# arduinoVisor3.net
KiCad netlist of a schematic drawn in EAGLE
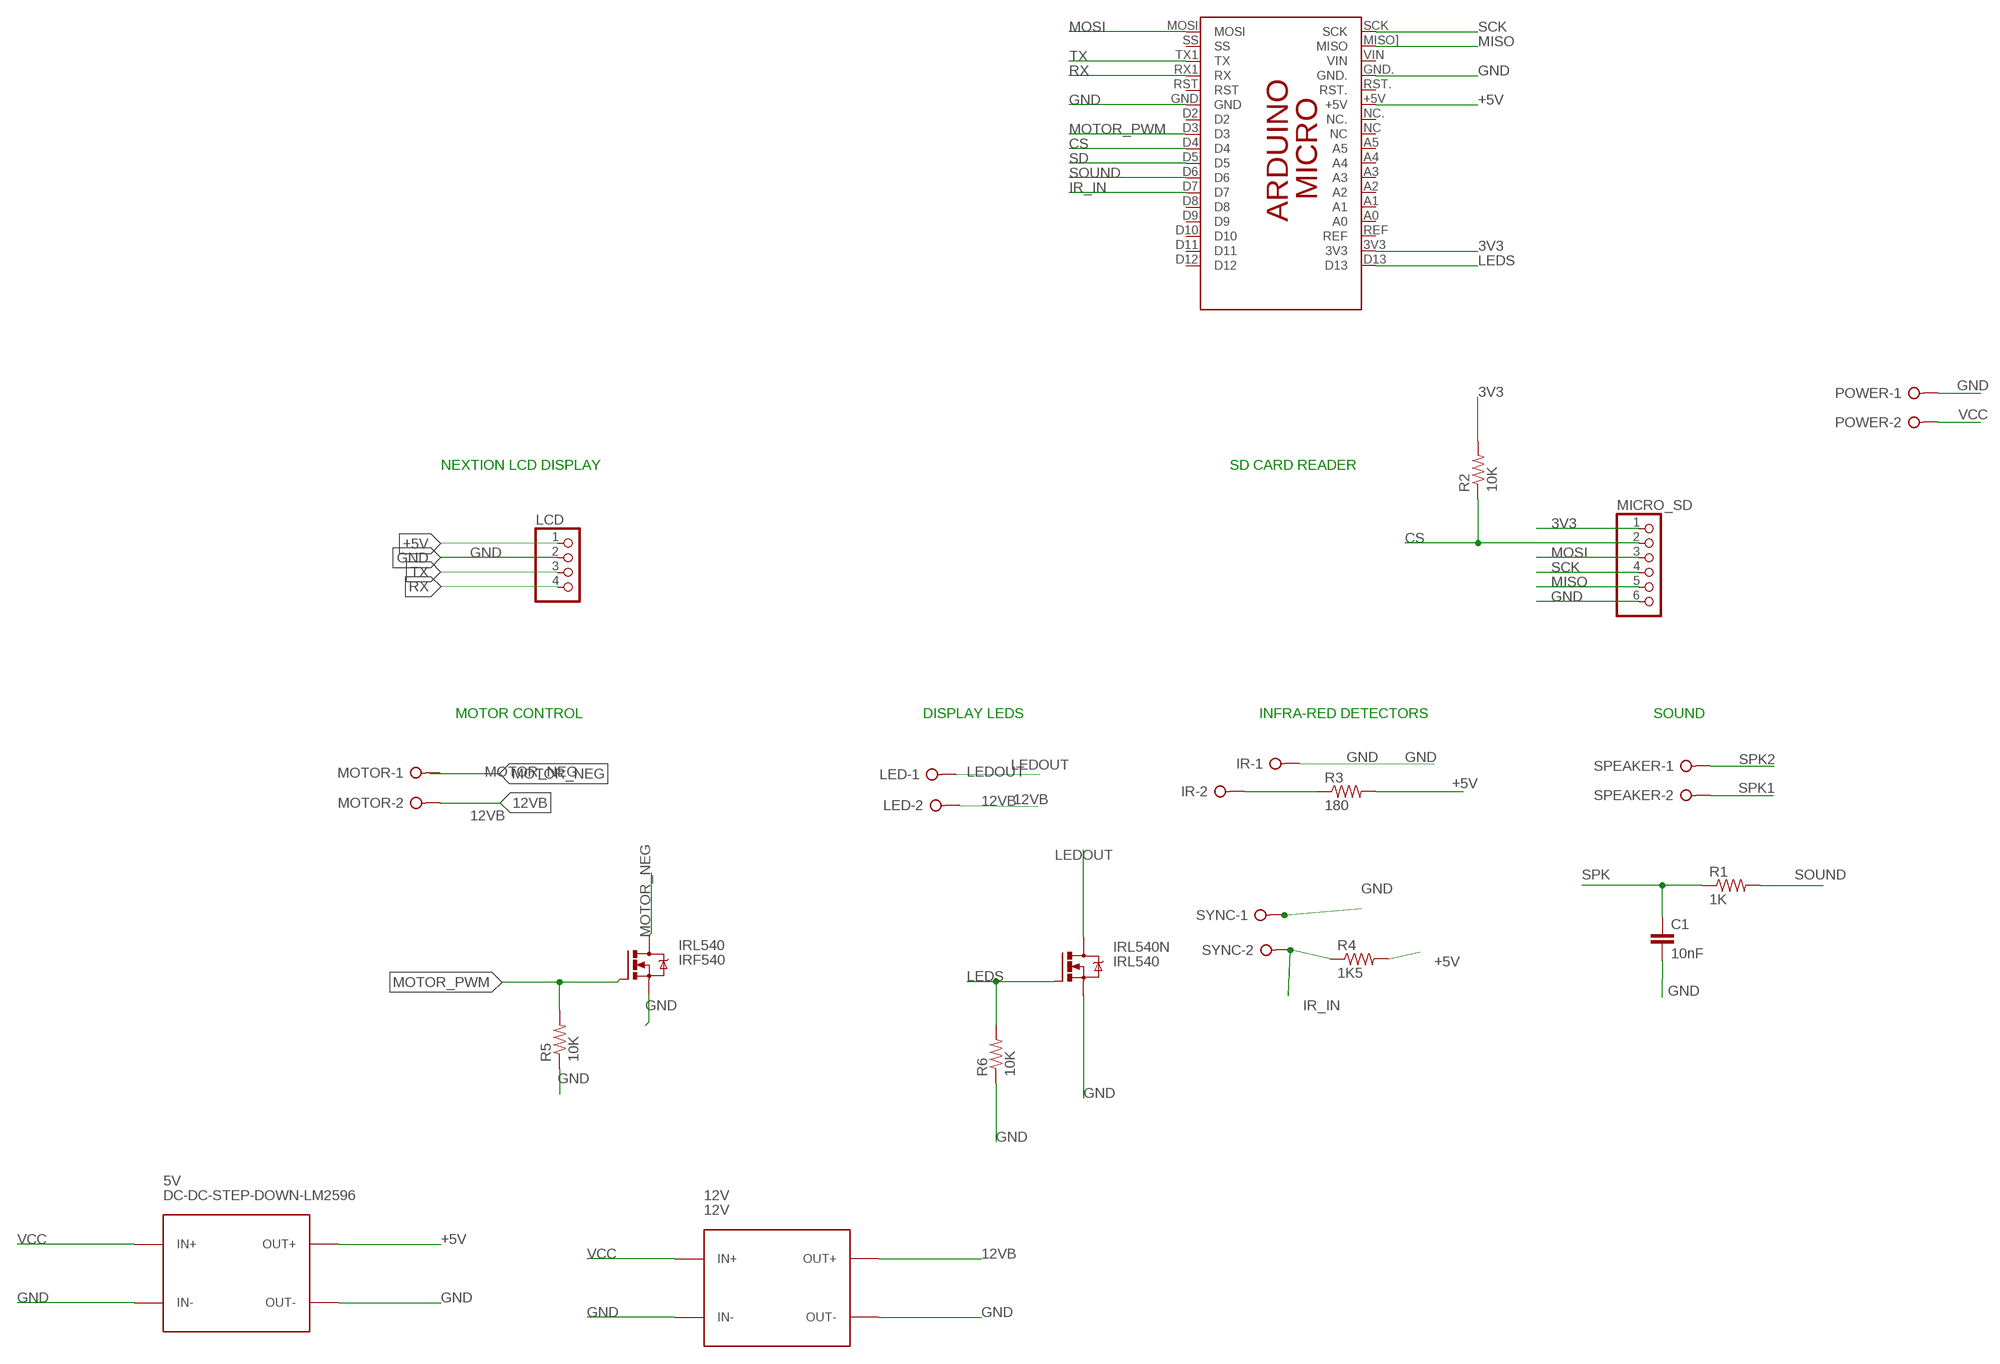
[diagram p0: schematic, sheet 1]
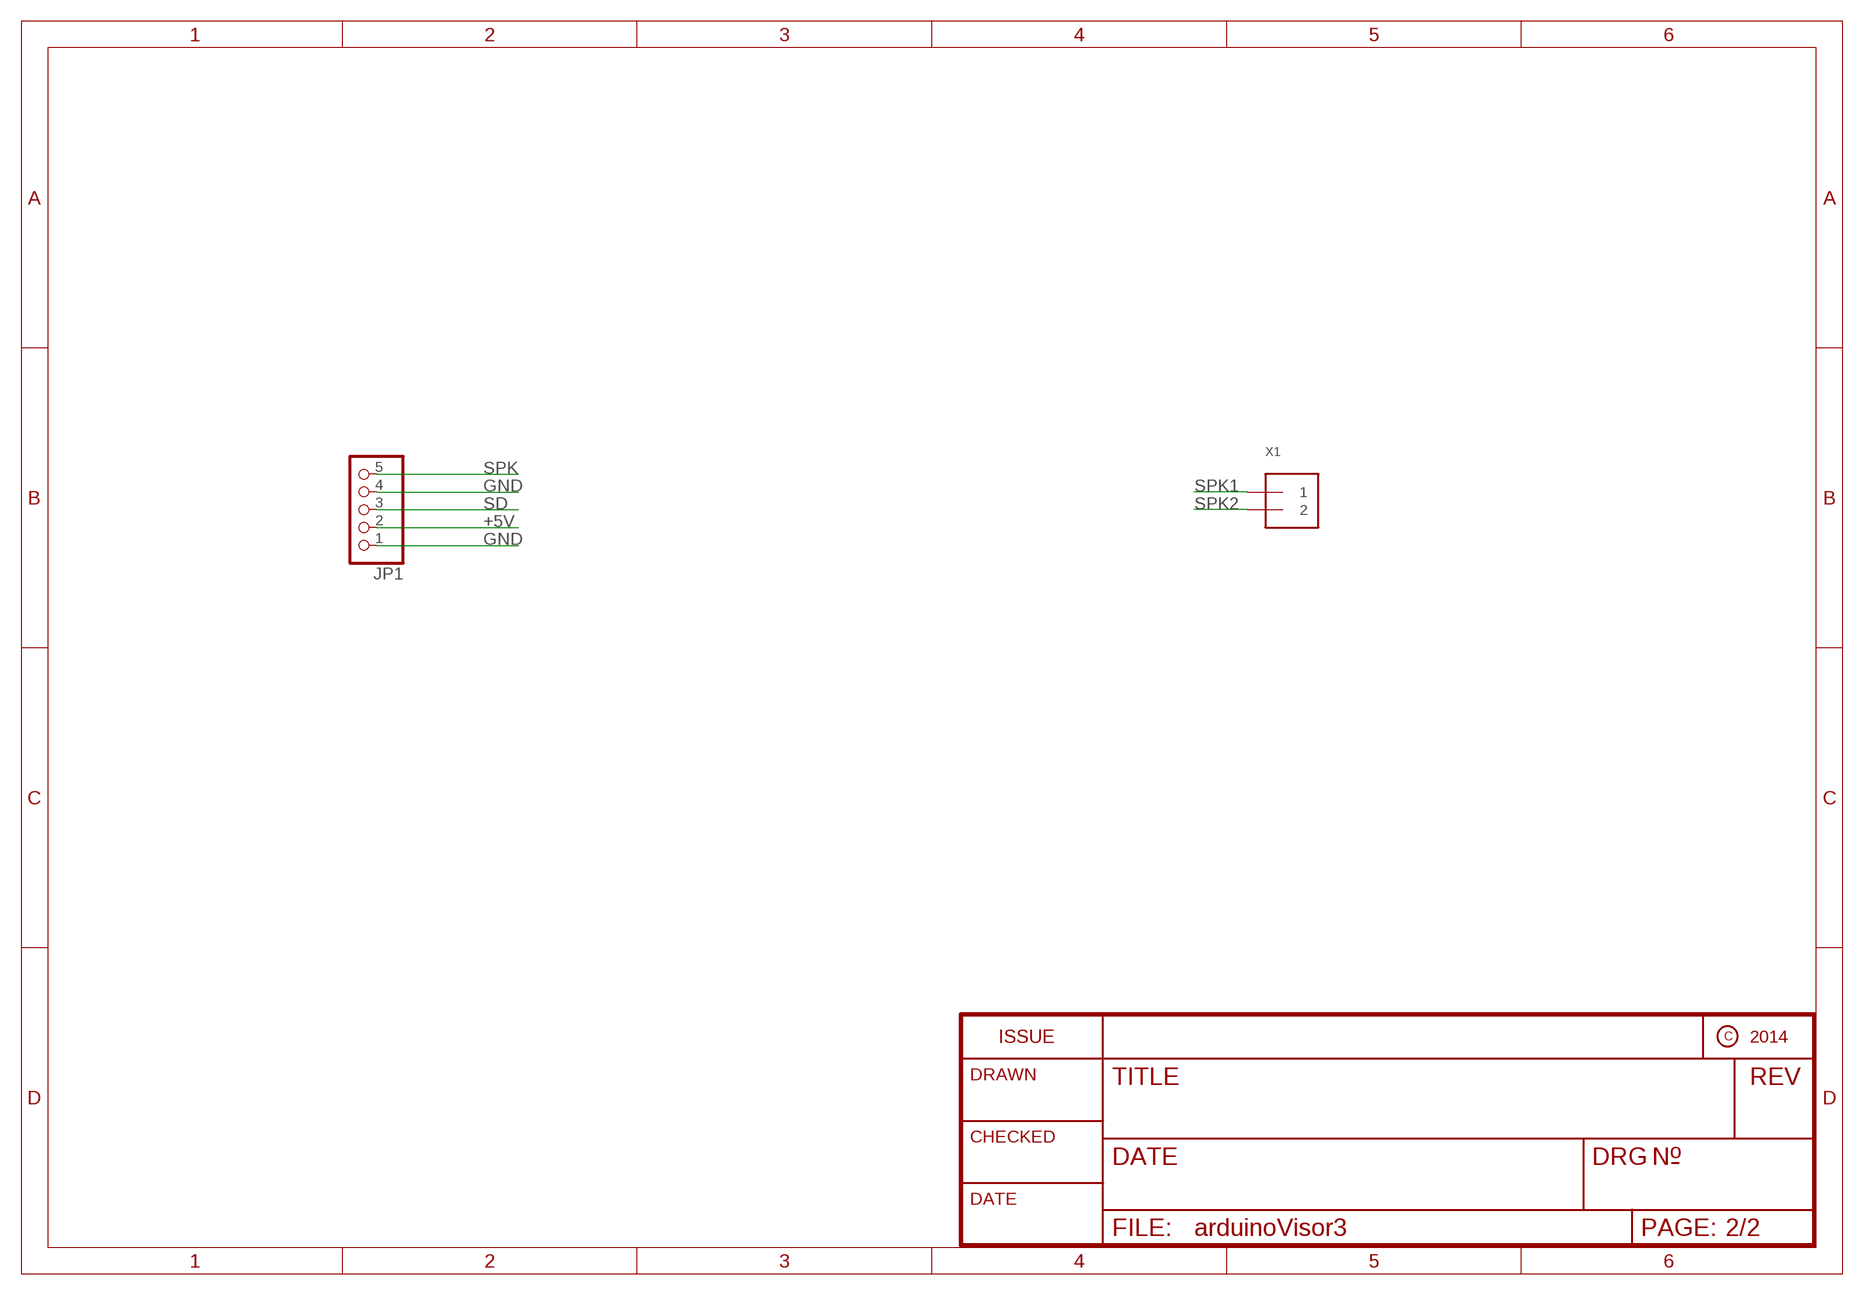
[diagram p1: schematic, sheet 2]

(export (version "E")
  (design (tool "Eeschema 10.0.6"))
  (components
    (comp (ref "5V")
      (value "DC-DC-STEP-DOWN-LM2596")
      (footprint "eagle-import:DC-DC-STEP-DOWN-LM2596")
      (libsource (lib "eagle-import") (part "DC-DC-STEP-DOWN-LM2596"))
    )
    (comp (ref "12V")
      (value "12V")
      (footprint "eagle-import:DC-DC-STEP-DOWN-LM2596")
      (libsource (lib "eagle-import") (part "DC-DC-STEP-DOWN-LM2596"))
    )
    (comp (ref "C1")
      (value "10nF")
      (footprint "eagle-import:C2.5-2")
      (libsource (lib "eagle-import") (part "C2.5/2"))
    )
    (comp (ref "IR")
      (value "W237-02P")
      (footprint "eagle-import:W237-132")
      (libsource (lib "eagle-import") (part "W237-02P"))
    )
    (comp (ref "IRL540")
      (value "IRF540")
      (footprint "eagle-import:TO220BV")
      (libsource (lib "eagle-import") (part "IRF540"))
    )
    (comp (ref "IRL540N")
      (value "IRL540")
      (footprint "eagle-import:TO220BV")
      (libsource (lib "eagle-import") (part "IRF540"))
    )
    (comp (ref "LCD")
      (value "PINHD-1X4")
      (footprint "eagle-import:1X04")
      (libsource (lib "eagle-import") (part "PINHD-1X4"))
    )
    (comp (ref "LED")
      (value "W237-02P")
      (footprint "eagle-import:W237-132")
      (libsource (lib "eagle-import") (part "W237-02P"))
    )
    (comp (ref "MICRO_SD")
      (value "PINHD-1X6")
      (footprint "eagle-import:1X06")
      (libsource (lib "eagle-import") (part "PINHD-1X6"))
    )
    (comp (ref "MOTOR")
      (value "W237-02P")
      (footprint "eagle-import:W237-132")
      (libsource (lib "eagle-import") (part "W237-02P"))
    )
    (comp (ref "PCB2")
      (value "ARDUINO_MICRO")
      (footprint "eagle-import:ARDUINO_MICRO")
      (libsource (lib "eagle-import") (part "ARDUINO_MICRO"))
    )
    (comp (ref "POWER")
      (value "W237-02P")
      (footprint "eagle-import:W237-132")
      (libsource (lib "eagle-import") (part "W237-02P"))
    )
    (comp (ref "R1")
      (value "1K")
      (footprint "eagle-import:0207_10")
      (libsource (lib "eagle-import") (part "R-US_0207/10"))
    )
    (comp (ref "R2")
      (value "10K")
      (footprint "eagle-import:0207_10")
      (libsource (lib "eagle-import") (part "R-US_0207/10"))
    )
    (comp (ref "R3")
      (value "180")
      (footprint "eagle-import:0207_10")
      (libsource (lib "eagle-import") (part "R-US_0207/10"))
    )
    (comp (ref "R4")
      (value "1K5")
      (footprint "eagle-import:0207_10")
      (libsource (lib "eagle-import") (part "R-US_0207/10"))
    )
    (comp (ref "R5")
      (value "10K")
      (footprint "eagle-import:0207_10")
      (libsource (lib "eagle-import") (part "R-US_0207/10"))
    )
    (comp (ref "R6")
      (value "10K")
      (footprint "eagle-import:0207_10")
      (libsource (lib "eagle-import") (part "R-US_0207/10"))
    )
    (comp (ref "SPEAKER")
      (value "W237-02P")
      (footprint "eagle-import:W237-132")
      (libsource (lib "eagle-import") (part "W237-02P"))
    )
    (comp (ref "SYNC")
      (value "W237-02P")
      (footprint "eagle-import:W237-132")
      (libsource (lib "eagle-import") (part "W237-02P"))
    )
    (comp (ref "JP1")
      (value "HEADER-1X570MIL")
      (footprint "eagle-import:1X05_ROUND_70")
      (libsource (lib "eagle-import") (part "HEADER-1X570MIL"))
    )
    (comp (ref "X1")
      (value "TERMBLOCK_1X2")
      (footprint "eagle-import:TERMBLOCK_1X2-3.5MM")
      (libsource (lib "eagle-import") (part "TERMBLOCK_1X2"))
    )
  )
  (nets
    (net (code "1") (name "+5V") (class "Default")
      (node (ref "5V") (pin "OUT+") (pinfunction "OUT+_OUT+") (pintype "bidirectional"))
      (node (ref "JP1") (pin "2") (pinfunction "2_2") (pintype "passive"))
      (node (ref "LCD") (pin "1") (pinfunction "1_1") (pintype "passive"))
      (node (ref "PCB2") (pin "+5V") (pinfunction "+5V_+5V") (pintype "bidirectional"))
      (node (ref "R3") (pin "2") (pinfunction "2_2") (pintype "passive"))
      (node (ref "R4") (pin "2") (pinfunction "2_2") (pintype "passive"))
    )
    (net (code "2") (name "3V3") (class "Default")
      (node (ref "MICRO_SD") (pin "1") (pinfunction "1_1") (pintype "passive"))
      (node (ref "PCB2") (pin "3V3") (pinfunction "3V3_3V3") (pintype "bidirectional"))
      (node (ref "R2") (pin "2") (pinfunction "2_2") (pintype "passive"))
    )
    (net (code "3") (name "12VB") (class "Default")
      (node (ref "12V") (pin "OUT+") (pinfunction "OUT+_OUT+") (pintype "bidirectional"))
      (node (ref "LED") (pin "2") (pinfunction "KL_2") (pintype "passive"))
      (node (ref "MOTOR") (pin "2") (pinfunction "KL_2") (pintype "passive"))
    )
    (net (code "4") (name "CS") (class "Default")
      (node (ref "MICRO_SD") (pin "2") (pinfunction "2_2") (pintype "passive"))
      (node (ref "PCB2") (pin "D4") (pinfunction "D4_D4") (pintype "bidirectional"))
      (node (ref "R2") (pin "1") (pinfunction "1_1") (pintype "passive"))
    )
    (net (code "5") (name "GND") (class "Default")
      (node (ref "12V") (pin "IN-") (pinfunction "IN-_IN-") (pintype "bidirectional"))
      (node (ref "12V") (pin "OUT-") (pinfunction "OUT-_OUT-") (pintype "bidirectional"))
      (node (ref "5V") (pin "IN-") (pinfunction "IN-_IN-") (pintype "bidirectional"))
      (node (ref "5V") (pin "OUT-") (pinfunction "OUT-_OUT-") (pintype "bidirectional"))
      (node (ref "C1") (pin "2") (pinfunction "2_2") (pintype "passive"))
      (node (ref "IR") (pin "1") (pinfunction "KL_1") (pintype "passive"))
      (node (ref "IRL540") (pin "S") (pinfunction "S_S") (pintype "passive"))
      (node (ref "IRL540N") (pin "S") (pinfunction "S_S") (pintype "passive"))
      (node (ref "JP1") (pin "1") (pinfunction "1_1") (pintype "passive"))
      (node (ref "JP1") (pin "4") (pinfunction "4_4") (pintype "passive"))
      (node (ref "LCD") (pin "2") (pinfunction "2_2") (pintype "passive"))
      (node (ref "MICRO_SD") (pin "6") (pinfunction "6_6") (pintype "passive"))
      (node (ref "PCB2") (pin "GND") (pinfunction "GND_GND") (pintype "bidirectional"))
      (node (ref "PCB2") (pin "GND.") (pinfunction "GND._GND.") (pintype "bidirectional"))
      (node (ref "POWER") (pin "1") (pinfunction "KL_1") (pintype "passive"))
      (node (ref "R5") (pin "1") (pinfunction "1_1") (pintype "passive"))
      (node (ref "R6") (pin "1") (pinfunction "1_1") (pintype "passive"))
      (node (ref "SYNC") (pin "1") (pinfunction "KL_1") (pintype "passive"))
    )
    (net (code "6") (name "IR_IN") (class "Default")
      (node (ref "PCB2") (pin "D7") (pinfunction "D7_D7") (pintype "bidirectional"))
      (node (ref "R4") (pin "1") (pinfunction "1_1") (pintype "passive"))
      (node (ref "SYNC") (pin "2") (pinfunction "KL_2") (pintype "passive"))
    )
    (net (code "7") (name "LEDOUT") (class "Default")
      (node (ref "IRL540N") (pin "D") (pinfunction "D_D") (pintype "passive"))
      (node (ref "LED") (pin "1") (pinfunction "KL_1") (pintype "passive"))
    )
    (net (code "8") (name "LEDS") (class "Default")
      (node (ref "IRL540N") (pin "G") (pinfunction "G_G") (pintype "passive"))
      (node (ref "PCB2") (pin "D13") (pinfunction "D13_D13") (pintype "bidirectional"))
      (node (ref "R6") (pin "2") (pinfunction "2_2") (pintype "passive"))
    )
    (net (code "9") (name "MISO") (class "Default")
      (node (ref "MICRO_SD") (pin "5") (pinfunction "5_5") (pintype "passive"))
      (node (ref "PCB2") (pin "MISO]") (pinfunction "MISO_MISO]") (pintype "bidirectional"))
    )
    (net (code "10") (name "MOSI") (class "Default")
      (node (ref "MICRO_SD") (pin "3") (pinfunction "3_3") (pintype "passive"))
      (node (ref "PCB2") (pin "MOSI") (pinfunction "MOSI_MOSI") (pintype "bidirectional"))
    )
    (net (code "11") (name "MOTOR_NEG") (class "Default")
      (node (ref "IRL540") (pin "D") (pinfunction "D_D") (pintype "passive"))
      (node (ref "MOTOR") (pin "1") (pinfunction "KL_1") (pintype "passive"))
    )
    (net (code "12") (name "MOTOR_PWM") (class "Default")
      (node (ref "IRL540") (pin "G") (pinfunction "G_G") (pintype "passive"))
      (node (ref "PCB2") (pin "D3") (pinfunction "D3_D3") (pintype "bidirectional"))
      (node (ref "R5") (pin "2") (pinfunction "2_2") (pintype "passive"))
    )
    (net (code "13") (name "Net-(IRB-KL)") (class "Default")
      (node (ref "IR") (pin "2") (pinfunction "KL_2") (pintype "passive"))
      (node (ref "R3") (pin "1") (pinfunction "1_1") (pintype "passive"))
    )
    (net (code "14") (name "RX") (class "Default")
      (node (ref "LCD") (pin "4") (pinfunction "4_4") (pintype "passive"))
      (node (ref "PCB2") (pin "RX1") (pinfunction "RX_RX1") (pintype "bidirectional"))
    )
    (net (code "15") (name "SCK") (class "Default")
      (node (ref "MICRO_SD") (pin "4") (pinfunction "4_4") (pintype "passive"))
      (node (ref "PCB2") (pin "SCK") (pinfunction "SCK_SCK") (pintype "bidirectional"))
    )
    (net (code "16") (name "SD") (class "Default")
      (node (ref "JP1") (pin "3") (pinfunction "3_3") (pintype "passive"))
      (node (ref "PCB2") (pin "D5") (pinfunction "D5_D5") (pintype "bidirectional"))
    )
    (net (code "17") (name "SOUND") (class "Default")
      (node (ref "PCB2") (pin "D6") (pinfunction "D6_D6") (pintype "bidirectional"))
      (node (ref "R1") (pin "2") (pinfunction "2_2") (pintype "passive"))
    )
    (net (code "18") (name "SPK") (class "Default")
      (node (ref "C1") (pin "1") (pinfunction "1_1") (pintype "passive"))
      (node (ref "JP1") (pin "5") (pinfunction "5_5") (pintype "passive"))
      (node (ref "R1") (pin "1") (pinfunction "1_1") (pintype "passive"))
    )
    (net (code "19") (name "SPK1") (class "Default")
      (node (ref "SPEAKER") (pin "2") (pinfunction "KL_2") (pintype "passive"))
      (node (ref "X1") (pin "1") (pinfunction "1_1") (pintype "passive"))
    )
    (net (code "20") (name "SPK2") (class "Default")
      (node (ref "SPEAKER") (pin "1") (pinfunction "KL_1") (pintype "passive"))
      (node (ref "X1") (pin "2") (pinfunction "2_2") (pintype "passive"))
    )
    (net (code "21") (name "TX") (class "Default")
      (node (ref "LCD") (pin "3") (pinfunction "3_3") (pintype "passive"))
      (node (ref "PCB2") (pin "TX1") (pinfunction "TX_TX1") (pintype "bidirectional"))
    )
    (net (code "22") (name "VCC") (class "Default")
      (node (ref "12V") (pin "IN+") (pinfunction "IN+_IN+") (pintype "bidirectional"))
      (node (ref "5V") (pin "IN+") (pinfunction "IN+_IN+") (pintype "bidirectional"))
      (node (ref "POWER") (pin "2") (pinfunction "KL_2") (pintype "passive"))
    )
    (net (code "23") (name "unconnected-(PCB2-PadA0)") (class "Default")
      (node (ref "PCB2") (pin "A0") (pinfunction "A0_A0") (pintype "bidirectional"))
    )
    (net (code "24") (name "unconnected-(PCB2-PadA1)") (class "Default")
      (node (ref "PCB2") (pin "A1") (pinfunction "A1_A1") (pintype "bidirectional"))
    )
    (net (code "25") (name "unconnected-(PCB2-PadA2)") (class "Default")
      (node (ref "PCB2") (pin "A2") (pinfunction "A2_A2") (pintype "bidirectional"))
    )
    (net (code "26") (name "unconnected-(PCB2-PadA3)") (class "Default")
      (node (ref "PCB2") (pin "A3") (pinfunction "A3_A3") (pintype "bidirectional"))
    )
    (net (code "27") (name "unconnected-(PCB2-PadA4)") (class "Default")
      (node (ref "PCB2") (pin "A4") (pinfunction "A4_A4") (pintype "bidirectional"))
    )
    (net (code "28") (name "unconnected-(PCB2-PadA5)") (class "Default")
      (node (ref "PCB2") (pin "A5") (pinfunction "A5_A5") (pintype "bidirectional"))
    )
    (net (code "29") (name "unconnected-(PCB2-PadD2)") (class "Default")
      (node (ref "PCB2") (pin "D2") (pinfunction "D2_D2") (pintype "bidirectional"))
    )
    (net (code "30") (name "unconnected-(PCB2-PadD8)") (class "Default")
      (node (ref "PCB2") (pin "D8") (pinfunction "D8_D8") (pintype "bidirectional"))
    )
    (net (code "31") (name "unconnected-(PCB2-PadD9)") (class "Default")
      (node (ref "PCB2") (pin "D9") (pinfunction "D9_D9") (pintype "bidirectional"))
    )
    (net (code "32") (name "unconnected-(PCB2-PadD10)") (class "Default")
      (node (ref "PCB2") (pin "D10") (pinfunction "D10_D10") (pintype "bidirectional"))
    )
    (net (code "33") (name "unconnected-(PCB2-PadD11)") (class "Default")
      (node (ref "PCB2") (pin "D11") (pinfunction "D11_D11") (pintype "bidirectional"))
    )
    (net (code "34") (name "unconnected-(PCB2-PadD12)") (class "Default")
      (node (ref "PCB2") (pin "D12") (pinfunction "D12_D12") (pintype "bidirectional"))
    )
    (net (code "35") (name "unconnected-(PCB2-PadNC)") (class "Default")
      (node (ref "PCB2") (pin "NC") (pinfunction "NC_NC") (pintype "bidirectional"))
    )
    (net (code "36") (name "unconnected-(PCB2-PadNC.)") (class "Default")
      (node (ref "PCB2") (pin "NC.") (pinfunction "NC._NC.") (pintype "bidirectional"))
    )
    (net (code "37") (name "unconnected-(PCB2-PadREF)") (class "Default")
      (node (ref "PCB2") (pin "REF") (pinfunction "REF_REF") (pintype "bidirectional"))
    )
    (net (code "38") (name "unconnected-(PCB2-PadRST)") (class "Default")
      (node (ref "PCB2") (pin "RST") (pinfunction "RST_RST") (pintype "bidirectional"))
    )
    (net (code "39") (name "unconnected-(PCB2-PadRST.)") (class "Default")
      (node (ref "PCB2") (pin "RST.") (pinfunction "RST._RST.") (pintype "bidirectional"))
    )
    (net (code "40") (name "unconnected-(PCB2-PadSS)") (class "Default")
      (node (ref "PCB2") (pin "SS") (pinfunction "SS_SS") (pintype "bidirectional"))
    )
    (net (code "41") (name "unconnected-(PCB2-PadVIN)") (class "Default")
      (node (ref "PCB2") (pin "VIN") (pinfunction "VIN_VIN") (pintype "bidirectional"))
    )
  )
)
